# HA_Out.net
KiCad netlist of a schematic drawn in Altium Designer
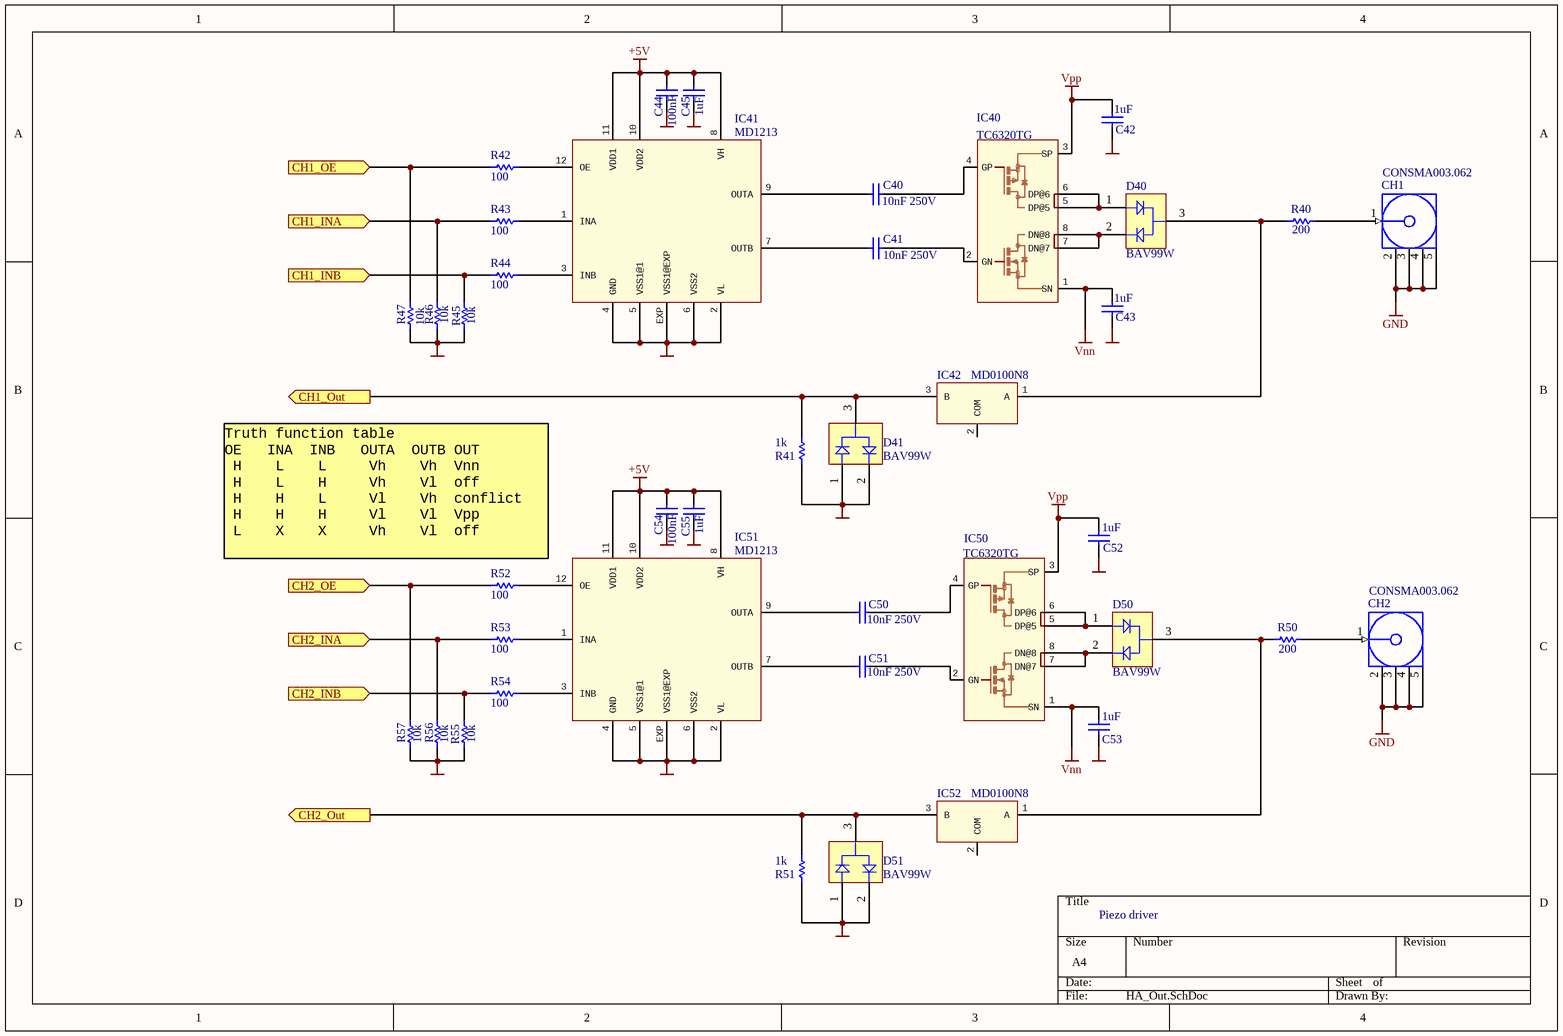
[diagram p0: HA_Out.SchDoc]

(export (version "E")
  (design (tool "Eeschema 10.0.6"))
  (components
    (comp (ref "C40")
      (value "10nF 250V")
      (footprint "CAPC0805(2012)75_N")
      (description "CAP 0805 (2012 Metric) Thickness 0.75mm SMD")
      (fields (field (name "TOLERANCE") "±10%"))
      (libsource (lib "Altium Content Vault") (part "CMP-1036-00417-1"))
    )
    (comp (ref "C41")
      (value "10nF 250V")
      (footprint "CAPC0805(2012)75_N")
      (description "CAP 0805 (2012 Metric) Thickness 0.75mm SMD")
      (fields (field (name "TOLERANCE") "±10%"))
      (libsource (lib "Altium Content Vault") (part "CMP-1036-00417-1"))
    )
    (comp (ref "C42")
      (value "1uF")
      (footprint "CAPC1206(3216)190_N")
      (description "CAP 1206 (3216 Metric) Thickness 1.9mm SMD")
      (fields (field (name "TOLERANCE") "Â±20%"))
      (libsource (lib "Altium Content Vault") (part "CMP-1037-04411-1"))
    )
    (comp (ref "C43")
      (value "1uF")
      (footprint "CAPC1206(3216)190_N")
      (description "CAP 1206 (3216 Metric) Thickness 1.9mm SMD")
      (fields (field (name "TOLERANCE") "Â±20%"))
      (libsource (lib "Altium Content Vault") (part "CMP-1037-04411-1"))
    )
    (comp (ref "C44")
      (value "100nF")
      (footprint "CAPC0805(2012)75_N")
      (fields (field (name "TOLERANCE") "±10%"))
      (libsource (lib "Altium Content Vault") (part "CMP-1036-00417-1"))
    )
    (comp (ref "C45")
      (value "1uF")
      (footprint "CAPC0805(2012)75_N")
      (fields (field (name "TOLERANCE") "±10%"))
      (libsource (lib "Altium Content Vault") (part "CMP-1036-00417-1"))
    )
    (comp (ref "C50")
      (value "10nF 250V")
      (footprint "CAPC0805(2012)75_N")
      (description "CAP 0805 (2012 Metric) Thickness 0.75mm SMD")
      (fields (field (name "TOLERANCE") "±10%"))
      (libsource (lib "Altium Content Vault") (part "CMP-1036-00417-1"))
    )
    (comp (ref "C51")
      (value "10nF 250V")
      (footprint "CAPC0805(2012)75_N")
      (description "CAP 0805 (2012 Metric) Thickness 0.75mm SMD")
      (fields (field (name "TOLERANCE") "±10%"))
      (libsource (lib "Altium Content Vault") (part "CMP-1036-00417-1"))
    )
    (comp (ref "C52")
      (value "1uF")
      (footprint "CAPC1206(3216)190_N")
      (description "CAP 1206 (3216 Metric) Thickness 1.9mm SMD")
      (fields (field (name "TOLERANCE") "Â±20%"))
      (libsource (lib "Altium Content Vault") (part "CMP-1037-04411-1"))
    )
    (comp (ref "C53")
      (value "1uF")
      (footprint "CAPC1206(3216)190_N")
      (description "CAP 1206 (3216 Metric) Thickness 1.9mm SMD")
      (fields (field (name "TOLERANCE") "Â±20%"))
      (libsource (lib "Altium Content Vault") (part "CMP-1037-04411-1"))
    )
    (comp (ref "C54")
      (value "100nF")
      (footprint "CAPC0805(2012)75_N")
      (fields (field (name "TOLERANCE") "±10%"))
      (libsource (lib "Altium Content Vault") (part "CMP-1036-00417-1"))
    )
    (comp (ref "C55")
      (value "1uF")
      (footprint "CAPC0805(2012)75_N")
      (fields (field (name "TOLERANCE") "±10%"))
      (libsource (lib "Altium Content Vault") (part "CMP-1036-00417-1"))
    )
    (comp (ref "CH1")
      (value "CONSMA003.062")
      (footprint "CON-SMA-EDGE062")
      (description "SMA Female Edge Mount Connector for 0.062\" Thick Board")
      (libsource (lib "Altium Content Vault") (part "CMP-0168-00029-1"))
    )
    (comp (ref "CH2")
      (value "CONSMA003.062")
      (footprint "CON-SMA-EDGE062")
      (description "SMA Female Edge Mount Connector for 0.062\" Thick Board")
      (libsource (lib "Altium Content Vault") (part "CMP-0168-00029-1"))
    )
    (comp (ref "D40")
      (value "BAV99W")
      (footprint "INF-SOT323_M")
      (description "Silicon Switching Diode, SOT323, Reel, Green")
      (fields (field (name "MANUFACTURER") "Diodes Inc") (field (name "MPN") "BAV99W-7-F"))
      (libsource (lib "") (part "CMP-1176-00026-1_1"))
    )
    (comp (ref "D41")
      (value "BAV99W")
      (footprint "INF-SOT323_M")
      (description "Silicon Switching Diode, SOT323, Reel, Green")
      (fields (field (name "MANUFACTURER") "Diodes Inc") (field (name "MPN") "BAV99W-7-F"))
      (libsource (lib "Altium Content Vault") (part "CMP-1176-00026-1"))
    )
    (comp (ref "D50")
      (value "BAV99W")
      (footprint "INF-SOT323_M")
      (description "Silicon Switching Diode, SOT323, Reel, Green")
      (fields (field (name "MANUFACTURER") "Diodes Inc") (field (name "MPN") "BAV99W-7-F"))
      (libsource (lib "") (part "CMP-1176-00026-1_1"))
    )
    (comp (ref "D51")
      (value "BAV99W")
      (footprint "INF-SOT323_M")
      (description "Silicon Switching Diode, SOT323, Reel, Green")
      (fields (field (name "MANUFACTURER") "Diodes Inc") (field (name "MPN") "BAV99W-7-F"))
      (libsource (lib "Altium Content Vault") (part "CMP-1176-00026-1"))
    )
    (comp (ref "IC40")
      (value "TC6320TG")
      (footprint "SO08")
      (fields (field (name "MANUFACTURER") "Microchip") (field (name "MPN") "TC6320TG-G"))
      (libsource (lib "microchip") (part "TC6320"))
    )
    (comp (ref "IC41")
      (value "MD1213")
      (footprint "AMS-QFN-12-4000X4000DE-2125X2125TP_L")
      (fields (field (name "MANUFACTURER") "Microchip") (field (name "MPN") "MD1213K6-G"))
      (libsource (lib "microchip") (part "MD1213"))
    )
    (comp (ref "IC42")
      (value "MD0100N8")
      (footprint "SOT89")
      (fields (field (name "MPN") "MD0100N8-G") (field (name "MANUFACTURER") "Microchip"))
      (libsource (lib "microchip") (part "MD0100N8"))
    )
    (comp (ref "IC50")
      (value "TC6320TG")
      (footprint "SO08")
      (fields (field (name "MANUFACTURER") "Microchip") (field (name "MPN") "TC6320TG-G"))
      (libsource (lib "microchip") (part "TC6320"))
    )
    (comp (ref "IC51")
      (value "MD1213")
      (footprint "AMS-QFN-12-4000X4000DE-2125X2125TP_L")
      (fields (field (name "MANUFACTURER") "Microchip") (field (name "MPN") "MD1213K6-G"))
      (libsource (lib "microchip") (part "MD1213"))
    )
    (comp (ref "IC52")
      (value "MD0100N8")
      (footprint "SOT89")
      (fields (field (name "MANUFACTURER") "Microchip") (field (name "MPN") "MD0100N8-G"))
      (libsource (lib "microchip") (part "MD0100N8"))
    )
    (comp (ref "R40")
      (value "200")
      (footprint "RESC0805(2012)_L")
      (description "0.125W 1% 0805 (2012 Metric)  SMD")
      (fields (field (name "POWER") "0.125 W") (field (name "TOLERANCE") "1 %"))
      (libsource (lib "Altium Content Vault") (part "CMP-1013-00429-1"))
    )
    (comp (ref "R41")
      (value "1k")
      (footprint "RESC0805(2012)_L")
      (description "0.125W 1% 0805 (2012 Metric)  SMD")
      (fields (field (name "POWER") "0.125 W") (field (name "TOLERANCE") "1 %"))
      (libsource (lib "Altium Content Vault") (part "CMP-1013-00429-1"))
    )
    (comp (ref "R42")
      (value "100")
      (footprint "RESC0805(2012)_L")
      (description "0.125W 1% 0805 (2012 Metric)  SMD")
      (fields (field (name "POWER") "0.125 W") (field (name "TOLERANCE") "1 %"))
      (libsource (lib "Altium Content Vault") (part "CMP-1013-00429-1"))
    )
    (comp (ref "R43")
      (value "100")
      (footprint "RESC0805(2012)_L")
      (description "0.125W 1% 0805 (2012 Metric)  SMD")
      (fields (field (name "POWER") "0.125 W") (field (name "TOLERANCE") "1 %"))
      (libsource (lib "Altium Content Vault") (part "CMP-1013-00429-1"))
    )
    (comp (ref "R44")
      (value "100")
      (footprint "RESC0805(2012)_L")
      (description "0.125W 1% 0805 (2012 Metric)  SMD")
      (fields (field (name "POWER") "0.125 W") (field (name "TOLERANCE") "1 %"))
      (libsource (lib "Altium Content Vault") (part "CMP-1013-00429-1"))
    )
    (comp (ref "R45")
      (value "10k")
      (footprint "RESC0805(2012)_L")
      (description "0.125W 1% 0805 (2012 Metric)  SMD")
      (fields (field (name "POWER") "0.125 W") (field (name "TOLERANCE") "1 %"))
      (libsource (lib "Altium Content Vault") (part "CMP-1013-00429-1"))
    )
    (comp (ref "R46")
      (value "10k")
      (footprint "RESC0805(2012)_L")
      (description "0.125W 1% 0805 (2012 Metric)  SMD")
      (fields (field (name "POWER") "0.125 W") (field (name "TOLERANCE") "1 %"))
      (libsource (lib "Altium Content Vault") (part "CMP-1013-00429-1"))
    )
    (comp (ref "R47")
      (value "10k")
      (footprint "RESC0805(2012)_L")
      (description "0.125W 1% 0805 (2012 Metric)  SMD")
      (fields (field (name "POWER") "0.125 W") (field (name "TOLERANCE") "1 %"))
      (libsource (lib "Altium Content Vault") (part "CMP-1013-00429-1"))
    )
    (comp (ref "R50")
      (value "200")
      (footprint "RESC0805(2012)_L")
      (description "0.125W 1% 0805 (2012 Metric)  SMD")
      (fields (field (name "POWER") "0.125 W") (field (name "TOLERANCE") "1 %"))
      (libsource (lib "Altium Content Vault") (part "CMP-1013-00429-1"))
    )
    (comp (ref "R51")
      (value "1k")
      (footprint "RESC0805(2012)_L")
      (description "0.125W 1% 0805 (2012 Metric)  SMD")
      (fields (field (name "POWER") "0.125 W") (field (name "TOLERANCE") "1 %"))
      (libsource (lib "Altium Content Vault") (part "CMP-1013-00429-1"))
    )
    (comp (ref "R52")
      (value "100")
      (footprint "RESC0805(2012)_L")
      (description "0.125W 1% 0805 (2012 Metric)  SMD")
      (fields (field (name "POWER") "0.125 W") (field (name "TOLERANCE") "1 %"))
      (libsource (lib "Altium Content Vault") (part "CMP-1013-00429-1"))
    )
    (comp (ref "R53")
      (value "100")
      (footprint "RESC0805(2012)_L")
      (description "0.125W 1% 0805 (2012 Metric)  SMD")
      (fields (field (name "POWER") "0.125 W") (field (name "TOLERANCE") "1 %"))
      (libsource (lib "Altium Content Vault") (part "CMP-1013-00429-1"))
    )
    (comp (ref "R54")
      (value "100")
      (footprint "RESC0805(2012)_L")
      (description "0.125W 1% 0805 (2012 Metric)  SMD")
      (fields (field (name "POWER") "0.125 W") (field (name "TOLERANCE") "1 %"))
      (libsource (lib "Altium Content Vault") (part "CMP-1013-00429-1"))
    )
    (comp (ref "R55")
      (value "10k")
      (footprint "RESC0805(2012)_L")
      (description "0.125W 1% 0805 (2012 Metric)  SMD")
      (fields (field (name "POWER") "0.125 W") (field (name "TOLERANCE") "1 %"))
      (libsource (lib "Altium Content Vault") (part "CMP-1013-00429-1"))
    )
    (comp (ref "R56")
      (value "10k")
      (footprint "RESC0805(2012)_L")
      (description "0.125W 1% 0805 (2012 Metric)  SMD")
      (fields (field (name "POWER") "0.125 W") (field (name "TOLERANCE") "1 %"))
      (libsource (lib "Altium Content Vault") (part "CMP-1013-00429-1"))
    )
    (comp (ref "R57")
      (value "10k")
      (footprint "RESC0805(2012)_L")
      (description "0.125W 1% 0805 (2012 Metric)  SMD")
      (fields (field (name "POWER") "0.125 W") (field (name "TOLERANCE") "1 %"))
      (libsource (lib "Altium Content Vault") (part "CMP-1013-00429-1"))
    )
  )
  (nets
    (net (code "1") (name "+5V") (class "Default")
      (node (ref "C44") (pin "2") (pinfunction "2_2") (pintype "passive"))
      (node (ref "C45") (pin "2") (pinfunction "2_2") (pintype "passive"))
      (node (ref "C54") (pin "2") (pinfunction "2_2") (pintype "passive"))
      (node (ref "C55") (pin "2") (pinfunction "2_2") (pintype "passive"))
      (node (ref "IC41") (pin "10") (pinfunction "VDD2_10") (pintype "power_in"))
      (node (ref "IC41") (pin "11") (pinfunction "VDD1_11") (pintype "power_in"))
      (node (ref "IC41") (pin "8") (pinfunction "VH_8") (pintype "power_in"))
      (node (ref "IC51") (pin "10") (pinfunction "VDD2_10") (pintype "power_in"))
      (node (ref "IC51") (pin "11") (pinfunction "VDD1_11") (pintype "power_in"))
      (node (ref "IC51") (pin "8") (pinfunction "VH_8") (pintype "power_in"))
    )
    (net (code "2") (name "/CH1_INA") (class "Default")
      (node (ref "R43") (pin "1") (pinfunction "1_1") (pintype "passive"))
      (node (ref "R46") (pin "1") (pinfunction "1_1") (pintype "passive"))
    )
    (net (code "3") (name "/CH1_INB") (class "Default")
      (node (ref "R44") (pin "1") (pinfunction "1_1") (pintype "passive"))
      (node (ref "R45") (pin "1") (pinfunction "1_1") (pintype "passive"))
    )
    (net (code "4") (name "/CH1_OE") (class "Default")
      (node (ref "R42") (pin "1") (pinfunction "1_1") (pintype "passive"))
      (node (ref "R47") (pin "1") (pinfunction "1_1") (pintype "passive"))
    )
    (net (code "5") (name "/CH1_Out") (class "Default")
      (node (ref "D41") (pin "3") (pinfunction "C_3") (pintype "passive"))
      (node (ref "IC42") (pin "3") (pinfunction "B_3") (pintype "passive"))
      (node (ref "R41") (pin "1") (pinfunction "1_1") (pintype "passive"))
    )
    (net (code "6") (name "/CH2_INA") (class "Default")
      (node (ref "R53") (pin "1") (pinfunction "1_1") (pintype "passive"))
      (node (ref "R56") (pin "1") (pinfunction "1_1") (pintype "passive"))
    )
    (net (code "7") (name "/CH2_INB") (class "Default")
      (node (ref "R54") (pin "1") (pinfunction "1_1") (pintype "passive"))
      (node (ref "R55") (pin "1") (pinfunction "1_1") (pintype "passive"))
    )
    (net (code "8") (name "/CH2_OE") (class "Default")
      (node (ref "R52") (pin "1") (pinfunction "1_1") (pintype "passive"))
      (node (ref "R57") (pin "1") (pinfunction "1_1") (pintype "passive"))
    )
    (net (code "9") (name "/CH2_Out") (class "Default")
      (node (ref "D51") (pin "3") (pinfunction "C_3") (pintype "passive"))
      (node (ref "IC52") (pin "3") (pinfunction "B_3") (pintype "passive"))
      (node (ref "R51") (pin "1") (pinfunction "1_1") (pintype "passive"))
    )
    (net (code "10") (name "GND") (class "Default")
      (node (ref "C42") (pin "1") (pinfunction "1_1") (pintype "passive"))
      (node (ref "C43") (pin "1") (pinfunction "1_1") (pintype "passive"))
      (node (ref "C44") (pin "1") (pinfunction "1_1") (pintype "passive"))
      (node (ref "C45") (pin "1") (pinfunction "1_1") (pintype "passive"))
      (node (ref "C52") (pin "1") (pinfunction "1_1") (pintype "passive"))
      (node (ref "C53") (pin "1") (pinfunction "1_1") (pintype "passive"))
      (node (ref "C54") (pin "1") (pinfunction "1_1") (pintype "passive"))
      (node (ref "C55") (pin "1") (pinfunction "1_1") (pintype "passive"))
      (node (ref "CH1") (pin "2") (pinfunction "GND_2") (pintype "power_in"))
      (node (ref "CH1") (pin "3") (pinfunction "GND_3") (pintype "power_in"))
      (node (ref "CH1") (pin "4") (pinfunction "GND_4") (pintype "power_in"))
      (node (ref "CH1") (pin "5") (pinfunction "GND_5") (pintype "power_in"))
      (node (ref "CH2") (pin "2") (pinfunction "GND_2") (pintype "power_in"))
      (node (ref "CH2") (pin "3") (pinfunction "GND_3") (pintype "power_in"))
      (node (ref "CH2") (pin "4") (pinfunction "GND_4") (pintype "power_in"))
      (node (ref "CH2") (pin "5") (pinfunction "GND_5") (pintype "power_in"))
      (node (ref "D41") (pin "1") (pinfunction "A1_1") (pintype "passive"))
      (node (ref "D41") (pin "2") (pinfunction "K2_2") (pintype "passive"))
      (node (ref "D51") (pin "1") (pinfunction "A1_1") (pintype "passive"))
      (node (ref "D51") (pin "2") (pinfunction "K2_2") (pintype "passive"))
      (node (ref "IC41") (pin "2") (pinfunction "VL_2") (pintype "power_in"))
      (node (ref "IC41") (pin "4") (pinfunction "GND_4") (pintype "power_in"))
      (node (ref "IC41") (pin "5") (pinfunction "VSS1@1_5") (pintype "power_in"))
      (node (ref "IC41") (pin "6") (pinfunction "VSS2_6") (pintype "power_in"))
      (node (ref "IC41") (pin "EXP") (pinfunction "VSS1@EXP_EXP") (pintype "power_in"))
      (node (ref "IC51") (pin "2") (pinfunction "VL_2") (pintype "power_in"))
      (node (ref "IC51") (pin "4") (pinfunction "GND_4") (pintype "power_in"))
      (node (ref "IC51") (pin "5") (pinfunction "VSS1@1_5") (pintype "power_in"))
      (node (ref "IC51") (pin "6") (pinfunction "VSS2_6") (pintype "power_in"))
      (node (ref "IC51") (pin "EXP") (pinfunction "VSS1@EXP_EXP") (pintype "power_in"))
      (node (ref "R41") (pin "2") (pinfunction "2_2") (pintype "passive"))
      (node (ref "R45") (pin "2") (pinfunction "2_2") (pintype "passive"))
      (node (ref "R46") (pin "2") (pinfunction "2_2") (pintype "passive"))
      (node (ref "R47") (pin "2") (pinfunction "2_2") (pintype "passive"))
      (node (ref "R51") (pin "2") (pinfunction "2_2") (pintype "passive"))
      (node (ref "R55") (pin "2") (pinfunction "2_2") (pintype "passive"))
      (node (ref "R56") (pin "2") (pinfunction "2_2") (pintype "passive"))
      (node (ref "R57") (pin "2") (pinfunction "2_2") (pintype "passive"))
    )
    (net (code "11") (name "Net-(CH1-Signal)") (class "Default")
      (node (ref "CH1") (pin "1") (pinfunction "Signal_1") (pintype "input"))
      (node (ref "R40") (pin "2") (pinfunction "2_2") (pintype "passive"))
    )
    (net (code "12") (name "Net-(CH2-Signal)") (class "Default")
      (node (ref "CH2") (pin "1") (pinfunction "Signal_1") (pintype "input"))
      (node (ref "R50") (pin "2") (pinfunction "2_2") (pintype "passive"))
    )
    (net (code "13") (name "Net-(D40-A1)") (class "Default")
      (node (ref "D40") (pin "1") (pinfunction "A1_1") (pintype "passive"))
      (node (ref "IC40") (pin "5") (pinfunction "DP@5_5") (pintype "passive"))
      (node (ref "IC40") (pin "6") (pinfunction "DP@6_6") (pintype "passive"))
    )
    (net (code "14") (name "Net-(D40-C)") (class "Default")
      (node (ref "D40") (pin "3") (pinfunction "C_3") (pintype "passive"))
      (node (ref "IC42") (pin "1") (pinfunction "A_1") (pintype "passive"))
      (node (ref "R40") (pin "1") (pinfunction "1_1") (pintype "passive"))
    )
    (net (code "15") (name "Net-(D40-K2)") (class "Default")
      (node (ref "D40") (pin "2") (pinfunction "K2_2") (pintype "passive"))
      (node (ref "IC40") (pin "7") (pinfunction "DN@7_7") (pintype "passive"))
      (node (ref "IC40") (pin "8") (pinfunction "DN@8_8") (pintype "passive"))
    )
    (net (code "16") (name "Net-(D50-A1)") (class "Default")
      (node (ref "D50") (pin "1") (pinfunction "A1_1") (pintype "passive"))
      (node (ref "IC50") (pin "5") (pinfunction "DP@5_5") (pintype "passive"))
      (node (ref "IC50") (pin "6") (pinfunction "DP@6_6") (pintype "passive"))
    )
    (net (code "17") (name "Net-(D50-C)") (class "Default")
      (node (ref "D50") (pin "3") (pinfunction "C_3") (pintype "passive"))
      (node (ref "IC52") (pin "1") (pinfunction "A_1") (pintype "passive"))
      (node (ref "R50") (pin "1") (pinfunction "1_1") (pintype "passive"))
    )
    (net (code "18") (name "Net-(D50-K2)") (class "Default")
      (node (ref "D50") (pin "2") (pinfunction "K2_2") (pintype "passive"))
      (node (ref "IC50") (pin "7") (pinfunction "DN@7_7") (pintype "passive"))
      (node (ref "IC50") (pin "8") (pinfunction "DN@8_8") (pintype "passive"))
    )
    (net (code "19") (name "Net-(IC40-GN)") (class "Default")
      (node (ref "C41") (pin "1") (pinfunction "1_1") (pintype "passive"))
      (node (ref "IC40") (pin "2") (pinfunction "GN_2") (pintype "passive"))
    )
    (net (code "20") (name "Net-(IC40-GP)") (class "Default")
      (node (ref "C40") (pin "1") (pinfunction "1_1") (pintype "passive"))
      (node (ref "IC40") (pin "4") (pinfunction "GP_4") (pintype "passive"))
    )
    (net (code "21") (name "Net-(IC41-INA)") (class "Default")
      (node (ref "IC41") (pin "1") (pinfunction "INA_1") (pintype "passive"))
      (node (ref "R43") (pin "2") (pinfunction "2_2") (pintype "passive"))
    )
    (net (code "22") (name "Net-(IC41-INB)") (class "Default")
      (node (ref "IC41") (pin "3") (pinfunction "INB_3") (pintype "passive"))
      (node (ref "R44") (pin "2") (pinfunction "2_2") (pintype "passive"))
    )
    (net (code "23") (name "Net-(IC41-OE)") (class "Default")
      (node (ref "IC41") (pin "12") (pinfunction "OE_12") (pintype "passive"))
      (node (ref "R42") (pin "2") (pinfunction "2_2") (pintype "passive"))
    )
    (net (code "24") (name "Net-(IC41-OUTA)") (class "Default")
      (node (ref "C40") (pin "2") (pinfunction "2_2") (pintype "passive"))
      (node (ref "IC41") (pin "9") (pinfunction "OUTA_9") (pintype "passive"))
    )
    (net (code "25") (name "Net-(IC41-OUTB)") (class "Default")
      (node (ref "C41") (pin "2") (pinfunction "2_2") (pintype "passive"))
      (node (ref "IC41") (pin "7") (pinfunction "OUTB_7") (pintype "passive"))
    )
    (net (code "26") (name "Net-(IC50-GN)") (class "Default")
      (node (ref "C51") (pin "1") (pinfunction "1_1") (pintype "passive"))
      (node (ref "IC50") (pin "2") (pinfunction "GN_2") (pintype "passive"))
    )
    (net (code "27") (name "Net-(IC50-GP)") (class "Default")
      (node (ref "C50") (pin "1") (pinfunction "1_1") (pintype "passive"))
      (node (ref "IC50") (pin "4") (pinfunction "GP_4") (pintype "passive"))
    )
    (net (code "28") (name "Net-(IC51-INA)") (class "Default")
      (node (ref "IC51") (pin "1") (pinfunction "INA_1") (pintype "passive"))
      (node (ref "R53") (pin "2") (pinfunction "2_2") (pintype "passive"))
    )
    (net (code "29") (name "Net-(IC51-INB)") (class "Default")
      (node (ref "IC51") (pin "3") (pinfunction "INB_3") (pintype "passive"))
      (node (ref "R54") (pin "2") (pinfunction "2_2") (pintype "passive"))
    )
    (net (code "30") (name "Net-(IC51-OE)") (class "Default")
      (node (ref "IC51") (pin "12") (pinfunction "OE_12") (pintype "passive"))
      (node (ref "R52") (pin "2") (pinfunction "2_2") (pintype "passive"))
    )
    (net (code "31") (name "Net-(IC51-OUTA)") (class "Default")
      (node (ref "C50") (pin "2") (pinfunction "2_2") (pintype "passive"))
      (node (ref "IC51") (pin "9") (pinfunction "OUTA_9") (pintype "passive"))
    )
    (net (code "32") (name "Net-(IC51-OUTB)") (class "Default")
      (node (ref "C51") (pin "2") (pinfunction "2_2") (pintype "passive"))
      (node (ref "IC51") (pin "7") (pinfunction "OUTB_7") (pintype "passive"))
    )
    (net (code "33") (name "Vnn") (class "Default")
      (node (ref "C43") (pin "2") (pinfunction "2_2") (pintype "passive"))
      (node (ref "C53") (pin "2") (pinfunction "2_2") (pintype "passive"))
      (node (ref "IC40") (pin "1") (pinfunction "SN_1") (pintype "passive"))
      (node (ref "IC50") (pin "1") (pinfunction "SN_1") (pintype "passive"))
    )
    (net (code "34") (name "Vpp") (class "Default")
      (node (ref "C42") (pin "2") (pinfunction "2_2") (pintype "passive"))
      (node (ref "C52") (pin "2") (pinfunction "2_2") (pintype "passive"))
      (node (ref "IC40") (pin "3") (pinfunction "SP_3") (pintype "passive"))
      (node (ref "IC50") (pin "3") (pinfunction "SP_3") (pintype "passive"))
    )
    (net (code "35") (name "unconnected-(IC42-COM-Pad2)") (class "Default")
      (node (ref "IC42") (pin "2") (pinfunction "COM_2") (pintype "passive"))
    )
    (net (code "36") (name "unconnected-(IC52-COM-Pad2)") (class "Default")
      (node (ref "IC52") (pin "2") (pinfunction "COM_2") (pintype "passive"))
    )
  )
)
